# Alarm_Clock_Schemetic_final.net
KiCad netlist of a schematic drawn in Altium Designer
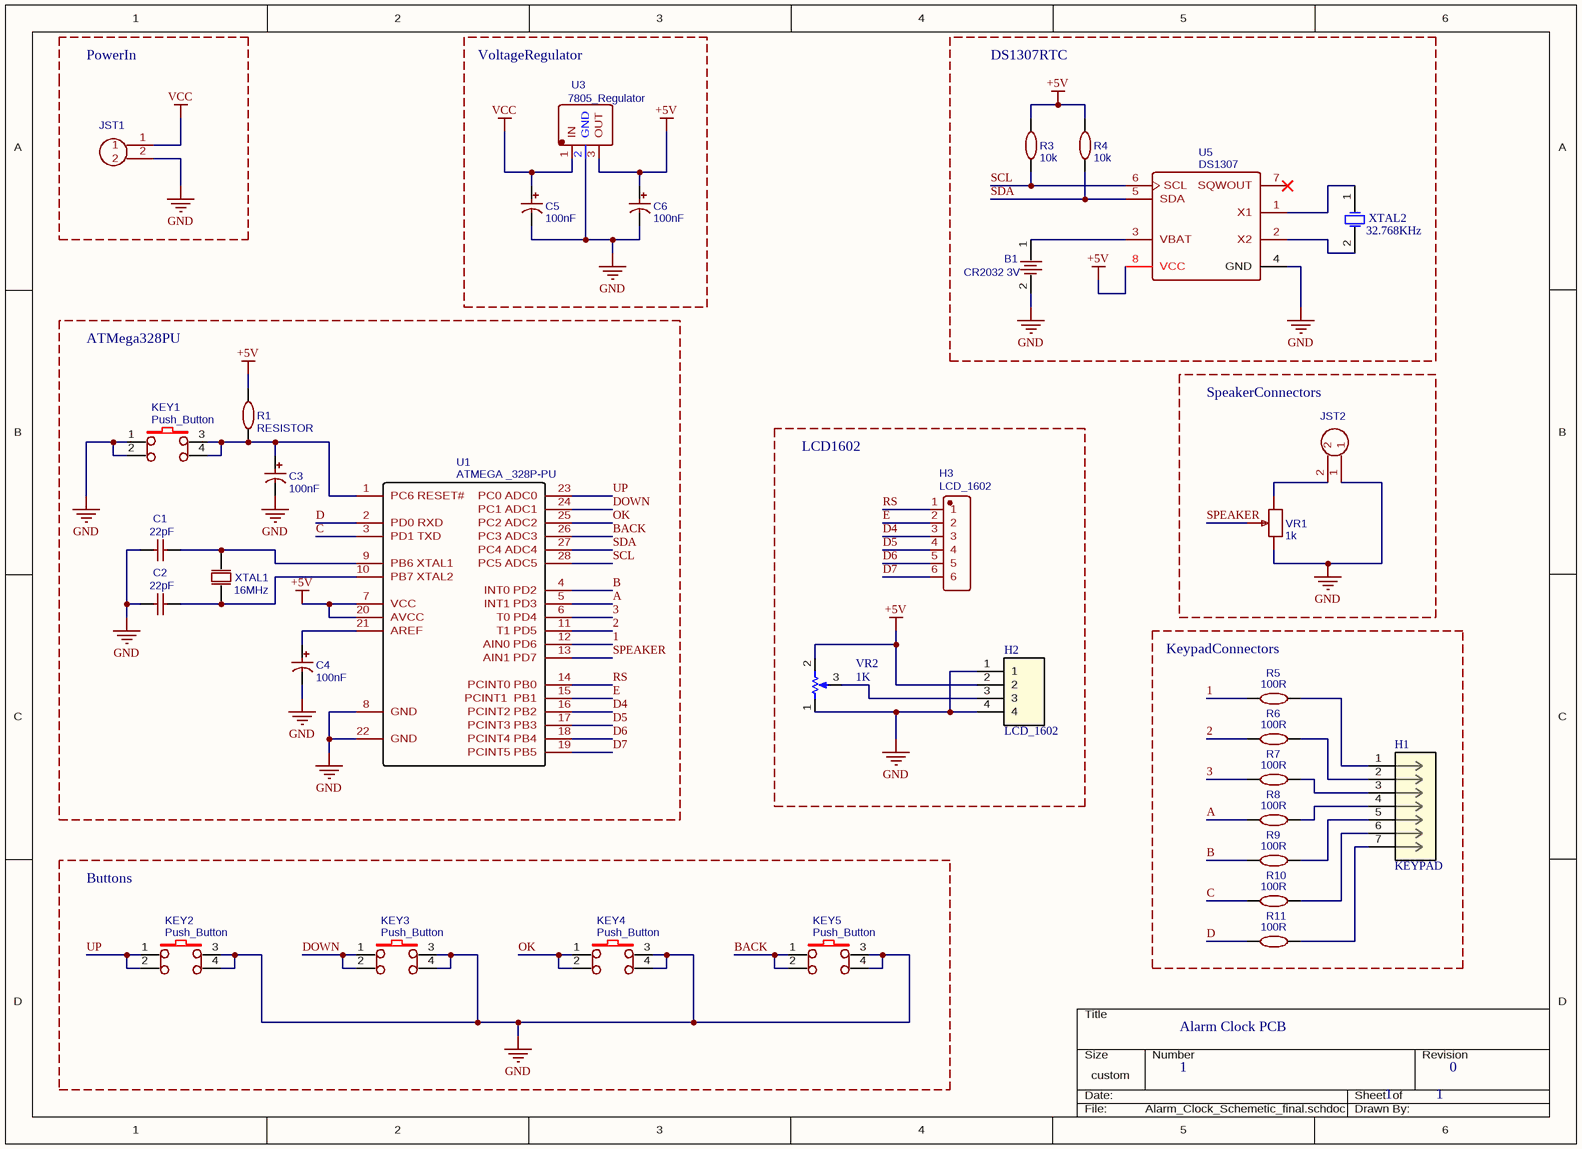
[diagram p0: Alarm_Clock_Schemetic_final.schdoc]

(export (version "E")
  (design (tool "Eeschema 10.0.6"))
  (components
    (comp (ref "B1")
      (value "CR2032 3V")
      (footprint "BAT-TH_BS-2-1")
      (fields (field (name "BOM_MANUFACTURER PART") "BS-2-1") (field (name "BOM_SUPPLIER PART") "C70376"))
      (libsource (lib "altium-import") (part "root_3_CR2032 3V_"))
    )
    (comp (ref "C1")
      (value "22pF")
      (footprint "RAD-0.2")
      (fields
        (field (name "BOM_MANUFACTURER PART") "0.1UF(104) +-20% 63v")
        (field (name "BOM_SUPPLIER PART") "C19355")
      )
      (libsource (lib "") (part "root_0_100nF__1"))
    )
    (comp (ref "C2")
      (value "22pF")
      (footprint "RAD-0.2")
      (fields
        (field (name "BOM_MANUFACTURER PART") "0.1UF(104) +-20% 63v")
        (field (name "BOM_SUPPLIER PART") "C19355")
      )
      (libsource (lib "") (part "root_0_100nF__1"))
    )
    (comp (ref "C3")
      (value "100nF")
      (footprint "CAP-TH_BD5.0-P2.00-D0.8-FD")
      (fields (field (name "BOM_MANUFACTURER PART") "0.1UF 50V") (field (name "BOM_SUPPLIER PART") "C28061"))
      (libsource (lib "altium-import") (part "root_0_100nF_"))
    )
    (comp (ref "C4")
      (value "100nF")
      (footprint "CAP-TH_BD5.0-P2.00-D0.8-FD")
      (fields (field (name "BOM_MANUFACTURER PART") "0.1UF 50V") (field (name "BOM_SUPPLIER PART") "C28061"))
      (libsource (lib "altium-import") (part "root_0_100nF_"))
    )
    (comp (ref "C5")
      (value "100nF")
      (footprint "CAP-TH_BD5.0-P2.00-D0.8-FD")
      (fields (field (name "BOM_MANUFACTURER PART") "0.1UF 50V") (field (name "BOM_SUPPLIER PART") "C28061"))
      (libsource (lib "altium-import") (part "root_0_100nF_"))
    )
    (comp (ref "C6")
      (value "100nF")
      (footprint "CAP-TH_BD5.0-P2.00-D0.8-FD")
      (fields (field (name "BOM_MANUFACTURER PART") "0.1UF 50V") (field (name "BOM_SUPPLIER PART") "C28061"))
      (libsource (lib "altium-import") (part "root_0_100nF_"))
    )
    (comp (ref "H1")
      (value "KEYPAD")
      (footprint "CON7_1X7_P100UM_HDR_TYC")
      (description "No Description Available")
      (fields
        (field (name "MANUFACTURER_PART_NUMBER") "826926-7")
        (field (name "COPYRIGHT") "Copyright (C) 2021 Ultra Librarian. All rights reserved.")
      )
      (libsource (lib "7pin_Header") (part "826926-7"))
    )
    (comp (ref "H2")
      (value "LCD_1602")
      (footprint "CON4_1X4_P100UM_HDR2_TYC")
      (description "No Description Available")
      (fields
        (field (name "MANUFACTURER_PART_NUMBER") "826936-4")
        (field (name "COPYRIGHT") "Copyright (C) 2021 Ultra Librarian. All rights reserved.")
      )
      (libsource (lib "4pin_Header") (part "826936-4"))
    )
    (comp (ref "H3")
      (value "LCD_1602")
      (footprint "HDR-TH_6P-P2.54-H-F-W5.7")
      (fields
        (field (name "BOM_SUPPLIER PART") "C2833720")
        (field (name "BOM_MANUFACTURER PART") "FFH25402-S06B1001K6K")
        (field (name "CONTRIBUTOR") "LCSC")
      )
      (libsource (lib "altium-import") (part "root_0_LCD_1602_"))
    )
    (comp (ref "JST1")
      (value "JST_2 PIN")
      (footprint "CONN-TH_XHB-2A")
      (fields
        (field (name "BOM_MANUFACTURER PART") "XHB-2A Connector")
        (field (name "BOM_SUPPLIER PART") "C57981")
      )
      (libsource (lib "altium-import") (part "root_0_JST_2 PIN_"))
    )
    (comp (ref "JST2")
      (value "JST_2 PIN")
      (footprint "CONN-TH_XHB-2A")
      (fields
        (field (name "BOM_MANUFACTURER PART") "XHB-2A Connector")
        (field (name "BOM_SUPPLIER PART") "C57981")
      )
      (libsource (lib "altium-import") (part "root_3_JST_2 PIN_"))
    )
    (comp (ref "KEY1")
      (value "Push_Button")
      (footprint "KEY-TH_4P-L6.0-W6.0-P4.50")
      (fields
        (field (name "BOM_SUPPLIER PART") "C59980")
        (field (name "BOM_MANUFACTURER PART") "button6*6*8.5")
      )
      (libsource (lib "altium-import") (part "root_0_Push_Button_"))
    )
    (comp (ref "KEY2")
      (value "Push_Button")
      (footprint "KEY-TH_4P-L6.0-W6.0-P4.50")
      (fields
        (field (name "BOM_SUPPLIER PART") "C59980")
        (field (name "BOM_MANUFACTURER PART") "button6*6*8.5")
      )
      (libsource (lib "altium-import") (part "root_0_Push_Button_"))
    )
    (comp (ref "KEY3")
      (value "Push_Button")
      (footprint "KEY-TH_4P-L6.0-W6.0-P4.50")
      (fields
        (field (name "BOM_SUPPLIER PART") "C59980")
        (field (name "BOM_MANUFACTURER PART") "button6*6*8.5")
      )
      (libsource (lib "altium-import") (part "root_0_Push_Button_"))
    )
    (comp (ref "KEY4")
      (value "Push_Button")
      (footprint "KEY-TH_4P-L6.0-W6.0-P4.50")
      (fields
        (field (name "BOM_SUPPLIER PART") "C59980")
        (field (name "BOM_MANUFACTURER PART") "button6*6*8.5")
      )
      (libsource (lib "altium-import") (part "root_0_Push_Button_"))
    )
    (comp (ref "KEY5")
      (value "Push_Button")
      (footprint "KEY-TH_4P-L6.0-W6.0-P4.50")
      (fields
        (field (name "BOM_SUPPLIER PART") "C59980")
        (field (name "BOM_MANUFACTURER PART") "button6*6*8.5")
      )
      (libsource (lib "altium-import") (part "root_0_Push_Button_"))
    )
    (comp (ref "R1")
      (value "RESISTOR")
      (footprint "AXIAL-0.4")
      (fields
        (field (name "POWER") "1/4W")
        (field (name "TOLERANCE") "±1%")
        (field (name "BOM_SUPPLIER PART") "E57439")
      )
      (libsource (lib "altium-import") (part "root_1_RESISTOR_"))
    )
    (comp (ref "R3")
      (value "10k")
      (footprint "AXIAL-0.4")
      (fields
        (field (name "POWER") "1/4W")
        (field (name "TOLERANCE") "±1%")
        (field (name "BOM_SUPPLIER PART") "E57439")
      )
      (libsource (lib "altium-import") (part "root_1_10k_"))
    )
    (comp (ref "R4")
      (value "10k")
      (footprint "AXIAL-0.4")
      (fields
        (field (name "POWER") "1/4W")
        (field (name "TOLERANCE") "±1%")
        (field (name "BOM_SUPPLIER PART") "E57439")
      )
      (libsource (lib "altium-import") (part "root_1_10k_"))
    )
    (comp (ref "R5")
      (value "100R")
      (footprint "AXIAL-0.4")
      (fields
        (field (name "POWER") "1/4W")
        (field (name "TOLERANCE") "±1%")
        (field (name "BOM_SUPPLIER PART") "E57439")
      )
      (libsource (lib "altium-import") (part "root_0_100R_"))
    )
    (comp (ref "R6")
      (value "100R")
      (footprint "AXIAL-0.4")
      (fields
        (field (name "POWER") "1/4W")
        (field (name "TOLERANCE") "±1%")
        (field (name "BOM_SUPPLIER PART") "E57439")
      )
      (libsource (lib "altium-import") (part "root_0_100R_"))
    )
    (comp (ref "R7")
      (value "100R")
      (footprint "AXIAL-0.4")
      (fields
        (field (name "POWER") "1/4W")
        (field (name "TOLERANCE") "±1%")
        (field (name "BOM_SUPPLIER PART") "E57439")
      )
      (libsource (lib "altium-import") (part "root_0_100R_"))
    )
    (comp (ref "R8")
      (value "100R")
      (footprint "AXIAL-0.4")
      (fields
        (field (name "POWER") "1/4W")
        (field (name "TOLERANCE") "±1%")
        (field (name "BOM_SUPPLIER PART") "E57439")
      )
      (libsource (lib "altium-import") (part "root_0_100R_"))
    )
    (comp (ref "R9")
      (value "100R")
      (footprint "AXIAL-0.4")
      (fields
        (field (name "POWER") "1/4W")
        (field (name "TOLERANCE") "±1%")
        (field (name "BOM_SUPPLIER PART") "E57439")
      )
      (libsource (lib "altium-import") (part "root_0_100R_"))
    )
    (comp (ref "R10")
      (value "100R")
      (footprint "AXIAL-0.4")
      (fields
        (field (name "POWER") "1/4W")
        (field (name "TOLERANCE") "±1%")
        (field (name "BOM_SUPPLIER PART") "E57439")
      )
      (libsource (lib "altium-import") (part "root_0_100R_"))
    )
    (comp (ref "R11")
      (value "100R")
      (footprint "AXIAL-0.4")
      (fields
        (field (name "POWER") "1/4W")
        (field (name "TOLERANCE") "±1%")
        (field (name "BOM_SUPPLIER PART") "E57439")
      )
      (libsource (lib "altium-import") (part "root_0_100R_"))
    )
    (comp (ref "U1")
      (value "ATMEGA _328P-PU")
      (footprint "DIP-28_L34.6-W7.3-P2.54-LS10.2-BL")
      (fields
        (field (name "BOM_MANUFACTURER PART") "ATMEGA328P-PU")
        (field (name "BOM_SUPPLIER PART") "C33901")
        (field (name "CONTRIBUTOR") "LCSC")
      )
      (libsource (lib "altium-import") (part "root_0_ATMEGA _328P-PU_"))
    )
    (comp (ref "U3")
      (value "7805_Regulator")
      (footprint "TO-220-3_L10.0-W4.5-P2.54-L")
      (fields
        (field (name "BOM_SUPPLIER PART") "C305416")
        (field (name "BOM_MANUFACTURER PART") "7805")
        (field (name "CONTRIBUTOR") "LCSC")
      )
      (libsource (lib "altium-import") (part "root_1_7805_Regulator_"))
    )
    (comp (ref "U5")
      (value "DS1307")
      (footprint "DIP-8_L9.8-W6.6-P2.54-LS7.6-BL")
      (fields (field (name "BOM_MANUFACTURER PART") "DS1307+") (field (name "BOM_SUPPLIER PART") "C59267"))
      (libsource (lib "altium-import") (part "root_0_DS1307_"))
    )
    (comp (ref "VR1")
      (value "1k")
      (footprint "RES-ADJ-TH_3296W")
      (fields (field (name "BOM_MANUFACTURER PART") "Pot-100R") (field (name "BOM_SUPPLIER PART") "C13649"))
      (libsource (lib "altium-import") (part "root_0_1k_"))
    )
    (comp (ref "VR2")
      (value "1K")
      (footprint "VR5")
      (description "Potentiometer")
      (fields (field (name "PUBLISHER") "Altium Limited"))
      (libsource (lib "Miscellaneous Devices") (part "RPot"))
    )
    (comp (ref "XTAL1")
      (value "16MHz")
      (footprint "16MHZ_OSC [PCB]")
      (fields
        (field (name "BOM_MANUFACTURER PART") "0SC-16MHz")
        (field (name "CONTRIBUTOR") "Mantas Petrauskas")
      )
      (libsource (lib "altium-import") (part "root_1_16MHz_"))
    )
    (comp (ref "XTAL2")
      (value "32.768KHz")
      (footprint "R38")
      (description "Crystal Oscillator")
      (fields (field (name "PUBLISHER") "Altium Limited"))
      (libsource (lib "Miscellaneous Devices") (part "XTAL"))
    )
  )
  (nets
    (net (code "1") (name "+5V") (class "Default")
      (node (ref "C6") (pin "1") (pinfunction "1_1") (pintype "passive"))
      (node (ref "H2") (pin "2") (pinfunction "2_2") (pintype "passive"))
      (node (ref "R1") (pin "2") (pinfunction "2_2") (pintype "passive"))
      (node (ref "R3") (pin "2") (pinfunction "2_2") (pintype "passive"))
      (node (ref "R4") (pin "2") (pinfunction "2_2") (pintype "passive"))
      (node (ref "U1") (pin "20") (pinfunction "AVCC_20") (pintype "passive"))
      (node (ref "U1") (pin "7") (pinfunction "VCC_7") (pintype "passive"))
      (node (ref "U3") (pin "3") (pinfunction "OUT_3") (pintype "passive"))
      (node (ref "U5") (pin "8") (pinfunction "VCC_8") (pintype "passive"))
      (node (ref "VR2") (pin "2") (pinfunction "BOT_2") (pintype "passive"))
    )
    (net (code "2") (name "/1") (class "Default")
      (node (ref "R5") (pin "1") (pinfunction "1_1") (pintype "passive"))
      (node (ref "U1") (pin "12") (pinfunction "AIN0_PD6_12") (pintype "passive"))
    )
    (net (code "3") (name "/2") (class "Default")
      (node (ref "R6") (pin "1") (pinfunction "1_1") (pintype "passive"))
      (node (ref "U1") (pin "11") (pinfunction "T1_PD5_11") (pintype "passive"))
    )
    (net (code "4") (name "/3") (class "Default")
      (node (ref "R7") (pin "1") (pinfunction "1_1") (pintype "passive"))
      (node (ref "U1") (pin "6") (pinfunction "T0_PD4_6") (pintype "passive"))
    )
    (net (code "5") (name "/A") (class "Default")
      (node (ref "R8") (pin "1") (pinfunction "1_1") (pintype "passive"))
      (node (ref "U1") (pin "5") (pinfunction "INT1_PD3_5") (pintype "passive"))
    )
    (net (code "6") (name "/B") (class "Default")
      (node (ref "R9") (pin "1") (pinfunction "1_1") (pintype "passive"))
      (node (ref "U1") (pin "4") (pinfunction "INT0_PD2_4") (pintype "passive"))
    )
    (net (code "7") (name "/BACK") (class "Default")
      (node (ref "KEY5") (pin "1") (pinfunction "1_1") (pintype "passive"))
      (node (ref "KEY5") (pin "2") (pinfunction "2_2") (pintype "passive"))
      (node (ref "U1") (pin "26") (pinfunction "PC3_ADC3_26") (pintype "passive"))
    )
    (net (code "8") (name "/C") (class "Default")
      (node (ref "R10") (pin "1") (pinfunction "1_1") (pintype "passive"))
      (node (ref "U1") (pin "3") (pinfunction "PD1_TXD_3") (pintype "passive"))
    )
    (net (code "9") (name "/D") (class "Default")
      (node (ref "R11") (pin "1") (pinfunction "1_1") (pintype "passive"))
      (node (ref "U1") (pin "2") (pinfunction "PD0_RXD_2") (pintype "passive"))
    )
    (net (code "10") (name "/D4") (class "Default")
      (node (ref "H3") (pin "3") (pinfunction "3_3") (pintype "passive"))
      (node (ref "U1") (pin "16") (pinfunction "PCINT2_PB2_16") (pintype "passive"))
    )
    (net (code "11") (name "/D5") (class "Default")
      (node (ref "H3") (pin "4") (pinfunction "4_4") (pintype "passive"))
      (node (ref "U1") (pin "17") (pinfunction "PCINT3_PB3_17") (pintype "passive"))
    )
    (net (code "12") (name "/D6") (class "Default")
      (node (ref "H3") (pin "5") (pinfunction "5_5") (pintype "passive"))
      (node (ref "U1") (pin "18") (pinfunction "PCINT4_PB4_18") (pintype "passive"))
    )
    (net (code "13") (name "/D7") (class "Default")
      (node (ref "H3") (pin "6") (pinfunction "6_6") (pintype "passive"))
      (node (ref "U1") (pin "19") (pinfunction "PCINT5_PB5_19") (pintype "passive"))
    )
    (net (code "14") (name "/DOWN") (class "Default")
      (node (ref "KEY3") (pin "1") (pinfunction "1_1") (pintype "passive"))
      (node (ref "KEY3") (pin "2") (pinfunction "2_2") (pintype "passive"))
      (node (ref "U1") (pin "24") (pinfunction "PC1_ADC1_24") (pintype "passive"))
    )
    (net (code "15") (name "/E") (class "Default")
      (node (ref "H3") (pin "2") (pinfunction "2_2") (pintype "passive"))
      (node (ref "U1") (pin "15") (pinfunction "PCINT1__PB1_15") (pintype "passive"))
    )
    (net (code "16") (name "/OK") (class "Default")
      (node (ref "KEY4") (pin "1") (pinfunction "1_1") (pintype "passive"))
      (node (ref "KEY4") (pin "2") (pinfunction "2_2") (pintype "passive"))
      (node (ref "U1") (pin "25") (pinfunction "PC2_ADC2_25") (pintype "passive"))
    )
    (net (code "17") (name "/RS") (class "Default")
      (node (ref "H3") (pin "1") (pinfunction "1_1") (pintype "passive"))
      (node (ref "U1") (pin "14") (pinfunction "PCINT0_PB0_14") (pintype "passive"))
    )
    (net (code "18") (name "/SCL") (class "Default")
      (node (ref "R3") (pin "1") (pinfunction "1_1") (pintype "passive"))
      (node (ref "U1") (pin "28") (pinfunction "PC5_ADC5_28") (pintype "passive"))
      (node (ref "U5") (pin "6") (pinfunction "SCL_6") (pintype "passive"))
    )
    (net (code "19") (name "/SDA") (class "Default")
      (node (ref "R4") (pin "1") (pinfunction "1_1") (pintype "passive"))
      (node (ref "U1") (pin "27") (pinfunction "PC4_ADC4_27") (pintype "passive"))
      (node (ref "U5") (pin "5") (pinfunction "SDA_5") (pintype "passive"))
    )
    (net (code "20") (name "/SPEAKER") (class "Default")
      (node (ref "U1") (pin "13") (pinfunction "AIN1_PD7_13") (pintype "passive"))
      (node (ref "VR1") (pin "2") (pinfunction "2_2") (pintype "passive"))
    )
    (net (code "21") (name "/UP") (class "Default")
      (node (ref "KEY2") (pin "1") (pinfunction "1_1") (pintype "passive"))
      (node (ref "KEY2") (pin "2") (pinfunction "2_2") (pintype "passive"))
      (node (ref "U1") (pin "23") (pinfunction "PC0_ADC0_23") (pintype "passive"))
    )
    (net (code "22") (name "GND") (class "Default")
      (node (ref "B1") (pin "2") (pinfunction "2_2") (pintype "passive"))
      (node (ref "C1") (pin "1") (pinfunction "1_1") (pintype "passive"))
      (node (ref "C2") (pin "1") (pinfunction "1_1") (pintype "passive"))
      (node (ref "C3") (pin "2") (pinfunction "2_2") (pintype "passive"))
      (node (ref "C4") (pin "2") (pinfunction "2_2") (pintype "passive"))
      (node (ref "C5") (pin "2") (pinfunction "2_2") (pintype "passive"))
      (node (ref "C6") (pin "2") (pinfunction "2_2") (pintype "passive"))
      (node (ref "H2") (pin "1") (pinfunction "1_1") (pintype "passive"))
      (node (ref "H2") (pin "4") (pinfunction "4_4") (pintype "passive"))
      (node (ref "JST1") (pin "2") (pinfunction "2_2") (pintype "passive"))
      (node (ref "JST2") (pin "1") (pinfunction "1_1") (pintype "passive"))
      (node (ref "KEY1") (pin "1") (pinfunction "1_1") (pintype "passive"))
      (node (ref "KEY1") (pin "2") (pinfunction "2_2") (pintype "passive"))
      (node (ref "KEY2") (pin "3") (pinfunction "3_3") (pintype "passive"))
      (node (ref "KEY2") (pin "4") (pinfunction "4_4") (pintype "passive"))
      (node (ref "KEY3") (pin "3") (pinfunction "3_3") (pintype "passive"))
      (node (ref "KEY3") (pin "4") (pinfunction "4_4") (pintype "passive"))
      (node (ref "KEY4") (pin "3") (pinfunction "3_3") (pintype "passive"))
      (node (ref "KEY4") (pin "4") (pinfunction "4_4") (pintype "passive"))
      (node (ref "KEY5") (pin "3") (pinfunction "3_3") (pintype "passive"))
      (node (ref "KEY5") (pin "4") (pinfunction "4_4") (pintype "passive"))
      (node (ref "U1") (pin "22") (pinfunction "GND_22") (pintype "passive"))
      (node (ref "U1") (pin "8") (pinfunction "GND_8") (pintype "passive"))
      (node (ref "U3") (pin "2") (pinfunction "GND_2") (pintype "passive"))
      (node (ref "U5") (pin "4") (pinfunction "GND_4") (pintype "passive"))
      (node (ref "VR1") (pin "3") (pinfunction "3_3") (pintype "passive"))
      (node (ref "VR2") (pin "1") (pinfunction "TOP_1") (pintype "passive"))
    )
    (net (code "23") (name "Net-(H1-Pad1)") (class "Default")
      (node (ref "H1") (pin "1") (pinfunction "1_1") (pintype "passive"))
      (node (ref "R5") (pin "2") (pinfunction "2_2") (pintype "passive"))
    )
    (net (code "24") (name "Net-(H1-Pad2)") (class "Default")
      (node (ref "H1") (pin "2") (pinfunction "2_2") (pintype "passive"))
      (node (ref "R6") (pin "2") (pinfunction "2_2") (pintype "passive"))
    )
    (net (code "25") (name "Net-(H1-Pad3)") (class "Default")
      (node (ref "H1") (pin "3") (pinfunction "3_3") (pintype "passive"))
      (node (ref "R7") (pin "2") (pinfunction "2_2") (pintype "passive"))
    )
    (net (code "26") (name "Net-(H1-Pad4)") (class "Default")
      (node (ref "H1") (pin "4") (pinfunction "4_4") (pintype "passive"))
      (node (ref "R8") (pin "2") (pinfunction "2_2") (pintype "passive"))
    )
    (net (code "27") (name "Net-(H1-Pad5)") (class "Default")
      (node (ref "H1") (pin "5") (pinfunction "5_5") (pintype "passive"))
      (node (ref "R9") (pin "2") (pinfunction "2_2") (pintype "passive"))
    )
    (net (code "28") (name "Net-(H1-Pad6)") (class "Default")
      (node (ref "H1") (pin "6") (pinfunction "6_6") (pintype "passive"))
      (node (ref "R10") (pin "2") (pinfunction "2_2") (pintype "passive"))
    )
    (net (code "29") (name "Net-(H1-Pad7)") (class "Default")
      (node (ref "H1") (pin "7") (pinfunction "7_7") (pintype "passive"))
      (node (ref "R11") (pin "2") (pinfunction "2_2") (pintype "passive"))
    )
    (net (code "30") (name "Net-(JST2-Pad2)") (class "Default")
      (node (ref "JST2") (pin "2") (pinfunction "2_2") (pintype "passive"))
      (node (ref "VR1") (pin "1") (pinfunction "1_1") (pintype "passive"))
    )
    (net (code "31") (name "Net-(U1-AREF)") (class "Default")
      (node (ref "C4") (pin "1") (pinfunction "1_1") (pintype "passive"))
      (node (ref "U1") (pin "21") (pinfunction "AREF_21") (pintype "passive"))
    )
    (net (code "32") (name "Net-(U1-PB6_XTAL1)") (class "Default")
      (node (ref "C1") (pin "2") (pinfunction "2_2") (pintype "passive"))
      (node (ref "U1") (pin "9") (pinfunction "PB6_XTAL1_9") (pintype "passive"))
      (node (ref "XTAL1") (pin "1") (pinfunction "OSC1_1") (pintype "passive"))
    )
    (net (code "33") (name "Net-(U1-PB7_XTAL2)") (class "Default")
      (node (ref "C2") (pin "2") (pinfunction "2_2") (pintype "passive"))
      (node (ref "U1") (pin "10") (pinfunction "PB7_XTAL2_10") (pintype "passive"))
      (node (ref "XTAL1") (pin "2") (pinfunction "OSC2_2") (pintype "passive"))
    )
    (net (code "34") (name "Net-(U1-PC6_RESET#)") (class "Default")
      (node (ref "C3") (pin "1") (pinfunction "1_1") (pintype "passive"))
      (node (ref "KEY1") (pin "3") (pinfunction "3_3") (pintype "passive"))
      (node (ref "KEY1") (pin "4") (pinfunction "4_4") (pintype "passive"))
      (node (ref "R1") (pin "1") (pinfunction "1_1") (pintype "passive"))
      (node (ref "U1") (pin "1") (pinfunction "PC6_RESET#_1") (pintype "passive"))
    )
    (net (code "35") (name "Net-(U5-VBAT)") (class "Default")
      (node (ref "B1") (pin "1") (pinfunction "1_1") (pintype "passive"))
      (node (ref "U5") (pin "3") (pinfunction "VBAT_3") (pintype "passive"))
    )
    (net (code "36") (name "Net-(U5-X1)") (class "Default")
      (node (ref "U5") (pin "1") (pinfunction "X1_1") (pintype "passive"))
      (node (ref "XTAL2") (pin "1") (pinfunction "OSC1_1") (pintype "passive"))
    )
    (net (code "37") (name "Net-(U5-X2)") (class "Default")
      (node (ref "U5") (pin "2") (pinfunction "X2_2") (pintype "passive"))
      (node (ref "XTAL2") (pin "2") (pinfunction "OSC2_2") (pintype "passive"))
    )
    (net (code "38") (name "Net-(VR2-TAP)") (class "Default")
      (node (ref "H2") (pin "3") (pinfunction "3_3") (pintype "passive"))
      (node (ref "VR2") (pin "3") (pinfunction "TAP_3") (pintype "passive"))
    )
    (net (code "39") (name "VCC") (class "Default")
      (node (ref "C5") (pin "1") (pinfunction "1_1") (pintype "passive"))
      (node (ref "JST1") (pin "1") (pinfunction "1_1") (pintype "passive"))
      (node (ref "U3") (pin "1") (pinfunction "IN_1") (pintype "passive"))
    )
    (net (code "40") (name "unconnected-(U5-SQWOUT-Pad7)") (class "Default")
      (node (ref "U5") (pin "7") (pinfunction "SQWOUT_7") (pintype "passive+no_connect"))
    )
  )
)
